# blink.net
KiCad netlist of a schematic drawn in Altium Designer
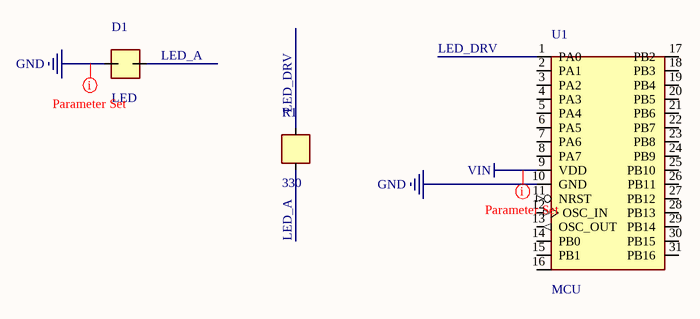
[diagram p0: blink.SchDoc]

(export (version "E")
  (design (tool "Eeschema 10.0.6"))
  (components
    (comp (ref "D1")
      (value "LED")
      (footprint "blink:Mini_LED_THT_3mm")
      (libsource (lib "blink") (part "Mini_LED"))
    )
    (comp (ref "R1") (value "330") (footprint "blink:Mini_R_0603") (libsource (lib "blink") (part "Mini_R")))
    (comp (ref "U1")
      (value "MCU")
      (footprint "blink:Mini_QFP-32_7x7mm_P0.8mm")
      (libsource (lib "blink") (part "Mini_QFP32_IC"))
    )
  )
  (nets
    (net (code "1") (name "/LED_A") (class "Default")
      (node (ref "D1") (pin "2") (pinfunction "A_2") (pintype "passive"))
      (node (ref "R1") (pin "2") (pintype "passive"))
    )
    (net (code "2") (name "/LED_DRV") (class "Default")
      (node (ref "R1") (pin "1") (pintype "passive"))
      (node (ref "U1") (pin "1") (pinfunction "PA0_1") (pintype "bidirectional"))
    )
    (net (code "3") (name "GND") (class "Default")
      (node (ref "D1") (pin "1") (pinfunction "K_1") (pintype "passive"))
      (node (ref "U1") (pin "10") (pinfunction "GND_10") (pintype "power_in"))
    )
    (net (code "4") (name "VIN") (class "Default")
      (node (ref "U1") (pin "9") (pinfunction "VDD_9") (pintype "power_in"))
    )
    (net (code "5") (name "unconnected-(U1-EP-Pad32)") (class "Default")
      (node (ref "U1") (pin "32") (pinfunction "EP_32") (pintype "passive"))
    )
    (net (code "6") (name "unconnected-(U1-NRST-Pad11)") (class "Default")
      (node (ref "U1") (pin "11") (pinfunction "NRST_11") (pintype "input"))
    )
    (net (code "7") (name "unconnected-(U1-OSC_IN-Pad12)") (class "Default")
      (node (ref "U1") (pin "12") (pinfunction "OSC_IN_12") (pintype "input"))
    )
    (net (code "8") (name "unconnected-(U1-OSC_OUT-Pad13)") (class "Default")
      (node (ref "U1") (pin "13") (pinfunction "OSC_OUT_13") (pintype "output"))
    )
    (net (code "9") (name "unconnected-(U1-PA1-Pad2)") (class "Default")
      (node (ref "U1") (pin "2") (pinfunction "PA1_2") (pintype "bidirectional"))
    )
    (net (code "10") (name "unconnected-(U1-PA2-Pad3)") (class "Default")
      (node (ref "U1") (pin "3") (pinfunction "PA2_3") (pintype "bidirectional"))
    )
    (net (code "11") (name "unconnected-(U1-PA3-Pad4)") (class "Default")
      (node (ref "U1") (pin "4") (pinfunction "PA3_4") (pintype "bidirectional"))
    )
    (net (code "12") (name "unconnected-(U1-PA4-Pad5)") (class "Default")
      (node (ref "U1") (pin "5") (pinfunction "PA4_5") (pintype "bidirectional"))
    )
    (net (code "13") (name "unconnected-(U1-PA5-Pad6)") (class "Default")
      (node (ref "U1") (pin "6") (pinfunction "PA5_6") (pintype "bidirectional"))
    )
    (net (code "14") (name "unconnected-(U1-PA6-Pad7)") (class "Default")
      (node (ref "U1") (pin "7") (pinfunction "PA6_7") (pintype "bidirectional"))
    )
    (net (code "15") (name "unconnected-(U1-PA7-Pad8)") (class "Default")
      (node (ref "U1") (pin "8") (pinfunction "PA7_8") (pintype "bidirectional"))
    )
    (net (code "16") (name "unconnected-(U1-PB0-Pad14)") (class "Default")
      (node (ref "U1") (pin "14") (pinfunction "PB0_14") (pintype "bidirectional"))
    )
    (net (code "17") (name "unconnected-(U1-PB1-Pad15)") (class "Default")
      (node (ref "U1") (pin "15") (pinfunction "PB1_15") (pintype "tri_state"))
    )
    (net (code "18") (name "unconnected-(U1-PB2-Pad17)") (class "Default")
      (node (ref "U1") (pin "17") (pinfunction "PB2_17") (pintype "bidirectional"))
    )
    (net (code "19") (name "unconnected-(U1-PB3-Pad18)") (class "Default")
      (node (ref "U1") (pin "18") (pinfunction "PB3_18") (pintype "bidirectional"))
    )
    (net (code "20") (name "unconnected-(U1-PB4-Pad19)") (class "Default")
      (node (ref "U1") (pin "19") (pinfunction "PB4_19") (pintype "bidirectional"))
    )
    (net (code "21") (name "unconnected-(U1-PB5-Pad20)") (class "Default")
      (node (ref "U1") (pin "20") (pinfunction "PB5_20") (pintype "bidirectional"))
    )
    (net (code "22") (name "unconnected-(U1-PB6-Pad21)") (class "Default")
      (node (ref "U1") (pin "21") (pinfunction "PB6_21") (pintype "bidirectional"))
    )
    (net (code "23") (name "unconnected-(U1-PB7-Pad22)") (class "Default")
      (node (ref "U1") (pin "22") (pinfunction "PB7_22") (pintype "bidirectional"))
    )
    (net (code "24") (name "unconnected-(U1-PB8-Pad23)") (class "Default")
      (node (ref "U1") (pin "23") (pinfunction "PB8_23") (pintype "bidirectional"))
    )
    (net (code "25") (name "unconnected-(U1-PB9-Pad24)") (class "Default")
      (node (ref "U1") (pin "24") (pinfunction "PB9_24") (pintype "bidirectional"))
    )
    (net (code "26") (name "unconnected-(U1-PB10-Pad25)") (class "Default")
      (node (ref "U1") (pin "25") (pinfunction "PB10_25") (pintype "bidirectional"))
    )
    (net (code "27") (name "unconnected-(U1-PB11-Pad26)") (class "Default")
      (node (ref "U1") (pin "26") (pinfunction "PB11_26") (pintype "bidirectional"))
    )
    (net (code "28") (name "unconnected-(U1-PB12-Pad27)") (class "Default")
      (node (ref "U1") (pin "27") (pinfunction "PB12_27") (pintype "bidirectional"))
    )
    (net (code "29") (name "unconnected-(U1-PB13-Pad28)") (class "Default")
      (node (ref "U1") (pin "28") (pinfunction "PB13_28") (pintype "bidirectional"))
    )
    (net (code "30") (name "unconnected-(U1-PB14-Pad29)") (class "Default")
      (node (ref "U1") (pin "29") (pinfunction "PB14_29") (pintype "bidirectional"))
    )
    (net (code "31") (name "unconnected-(U1-PB15-Pad30)") (class "Default")
      (node (ref "U1") (pin "30") (pinfunction "PB15_30") (pintype "bidirectional"))
    )
    (net (code "32") (name "unconnected-(U1-PB16-Pad31)") (class "Default")
      (node (ref "U1") (pin "31") (pinfunction "PB16_31") (pintype "bidirectional"))
    )
    (net (code "33") (name "unconnected-(U1-Pad16)") (class "Default")
      (node (ref "U1") (pin "16") (pintype "passive"))
    )
  )
)
